# pm-001.net
KiCad netlist of a schematic drawn in EAGLE
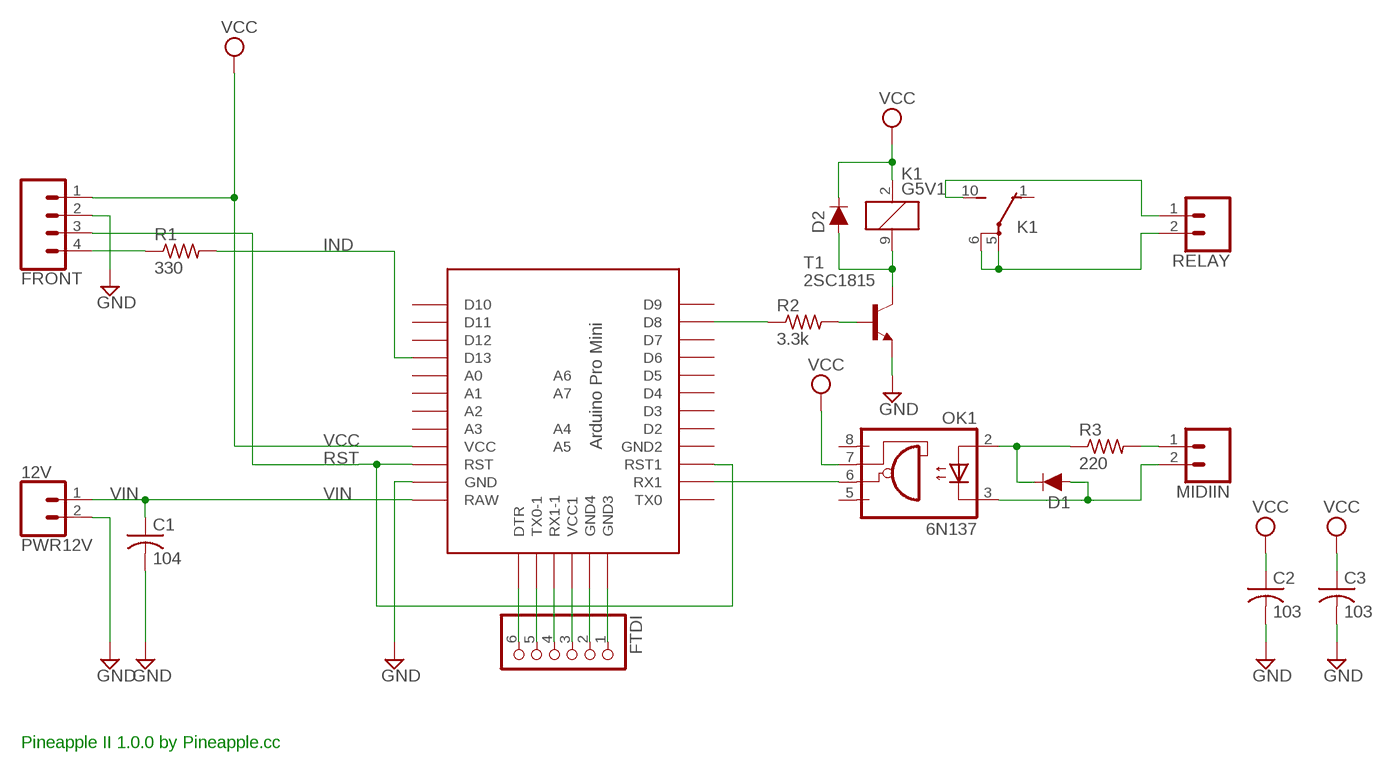
[diagram p0: schematic, sheet 1]

(export (version "E")
  (design (tool "Eeschema 10.0.6"))
  (components
    (comp (ref "C1")
      (value "104")
      (footprint "eagle-import:C025-025X050")
      (libsource (lib "eagle-import") (part "C-US025-025X050"))
    )
    (comp (ref "C2")
      (value "103")
      (footprint "eagle-import:C025-025X050")
      (libsource (lib "eagle-import") (part "C-US025-025X050"))
    )
    (comp (ref "C3")
      (value "103")
      (footprint "eagle-import:C025-025X050")
      (libsource (lib "eagle-import") (part "C-US025-025X050"))
    )
    (comp (ref "D1")
      (value "DIODE-1N4148")
      (footprint "eagle-import:DIODE-1N4148")
      (libsource (lib "eagle-import") (part "DIODE-1N4148"))
    )
    (comp (ref "D2")
      (value "DIODE-1N4148")
      (footprint "eagle-import:DIODE-1N4148")
      (libsource (lib "eagle-import") (part "DIODE-1N4148"))
    )
    (comp (ref "FRONT")
      (value "CONN_04JST-PTH")
      (footprint "eagle-import:JST-4-PTH")
      (libsource (lib "eagle-import") (part "CONN_04JST-PTH"))
    )
    (comp (ref "FTDI")
      (value "PINHD-1X6")
      (footprint "eagle-import:1X06")
      (libsource (lib "eagle-import") (part "PINHD-1X6"))
    )
    (comp (ref "K1")
      (value "G5V1")
      (footprint "eagle-import:G5V1")
      (fields (field (name "MPN") "G5V-1-DC24"))
      (libsource (lib "eagle-import") (part "G5V1"))
    )
    (comp (ref "MIDIIN")
      (value "CONN_02JST-PTH-2")
      (footprint "eagle-import:JST-2-PTH")
      (libsource (lib "eagle-import") (part "CONN_02JST-PTH-2"))
    )
    (comp (ref "OK1")
      (value "6N137")
      (footprint "eagle-import:DIL08")
      (libsource (lib "eagle-import") (part "6N137"))
    )
    (comp (ref "PWR12V")
      (value "12V")
      (footprint "eagle-import:JST-2-PTH")
      (libsource (lib "eagle-import") (part "CONN_02JST-PTH-2"))
    )
    (comp (ref "R1")
      (value "330")
      (footprint "eagle-import:0204_5")
      (libsource (lib "eagle-import") (part "R-US_0204/5"))
    )
    (comp (ref "R2")
      (value "3.3k")
      (footprint "eagle-import:0204_5")
      (libsource (lib "eagle-import") (part "R-US_0204/5"))
    )
    (comp (ref "R3")
      (value "220")
      (footprint "eagle-import:0204_5")
      (libsource (lib "eagle-import") (part "R-US_0204/5"))
    )
    (comp (ref "RELAY")
      (value "CONN_02JST-PTH-2")
      (footprint "eagle-import:JST-2-PTH")
      (libsource (lib "eagle-import") (part "CONN_02JST-PTH-2"))
    )
    (comp (ref "T1")
      (value "2SC1815")
      (footprint "eagle-import:TO92-ECB")
      (libsource (lib "eagle-import") (part "2SC1815"))
    )
    (comp (ref "U$1")
      (value "PRO-MINI-2")
      (footprint "eagle-import:PRO-MINI-2")
      (libsource (lib "eagle-import") (part "PRO-MINI-2"))
    )
  )
  (nets
    (net (code "1") (name "/IND") (class "Default")
      (node (ref "R1") (pin "2") (pinfunction "2_2") (pintype "passive"))
      (node (ref "U$1") (pin "D13") (pinfunction "D13_D13") (pintype "bidirectional"))
    )
    (net (code "2") (name "/RST") (class "Default")
      (node (ref "FRONT") (pin "3") (pinfunction "3_3") (pintype "passive"))
      (node (ref "U$1") (pin "RST") (pinfunction "RST_RST") (pintype "bidirectional"))
      (node (ref "U$1") (pin "RST1") (pinfunction "RST1_RST1") (pintype "bidirectional"))
    )
    (net (code "3") (name "/VIN") (class "Default")
      (node (ref "C1") (pin "1") (pinfunction "1_1") (pintype "passive"))
      (node (ref "PWR12V") (pin "1") (pinfunction "1_1") (pintype "passive"))
      (node (ref "U$1") (pin "RAW") (pinfunction "RAW_RAW") (pintype "bidirectional"))
    )
    (net (code "4") (name "GND") (class "Default")
      (node (ref "C1") (pin "2") (pinfunction "2_2") (pintype "passive"))
      (node (ref "C2") (pin "2") (pinfunction "2_2") (pintype "passive"))
      (node (ref "C3") (pin "2") (pinfunction "2_2") (pintype "passive"))
      (node (ref "FRONT") (pin "2") (pinfunction "2_2") (pintype "passive"))
      (node (ref "PWR12V") (pin "2") (pinfunction "2_2") (pintype "passive"))
      (node (ref "T1") (pin "E") (pinfunction "E_E") (pintype "passive"))
      (node (ref "U$1") (pin "GND") (pinfunction "GND_GND") (pintype "bidirectional"))
    )
    (net (code "5") (name "Net-(FRONT-Pad4)") (class "Default")
      (node (ref "FRONT") (pin "4") (pinfunction "4_4") (pintype "passive"))
      (node (ref "R1") (pin "1") (pinfunction "1_1") (pintype "passive"))
    )
    (net (code "6") (name "Net-(FTDI-Pad3)") (class "Default")
      (node (ref "FTDI") (pin "3") (pinfunction "3_3") (pintype "passive"))
      (node (ref "U$1") (pin "VCC1") (pinfunction "VCC1_VCC1") (pintype "bidirectional"))
    )
    (net (code "7") (name "Net-(FTDI-Pad4)") (class "Default")
      (node (ref "FTDI") (pin "4") (pinfunction "4_4") (pintype "passive"))
      (node (ref "U$1") (pin "RX1-1") (pinfunction "RX1-1_RX1-1") (pintype "bidirectional"))
    )
    (net (code "8") (name "Net-(FTDI-Pad5)") (class "Default")
      (node (ref "FTDI") (pin "5") (pinfunction "5_5") (pintype "passive"))
      (node (ref "U$1") (pin "TX0-1") (pinfunction "TX0-1_TX0-1") (pintype "bidirectional"))
    )
    (net (code "9") (name "Net-(FTDI-Pad6)") (class "Default")
      (node (ref "FTDI") (pin "6") (pinfunction "6_6") (pintype "passive"))
      (node (ref "U$1") (pin "DTR") (pinfunction "DTR_DTR") (pintype "bidirectional"))
    )
    (net (code "10") (name "Net-(K1A-2)") (class "Default")
      (node (ref "D2") (pin "A") (pinfunction "A_A") (pintype "passive"))
      (node (ref "K1") (pin "9") (pinfunction "2_9") (pintype "passive"))
      (node (ref "T1") (pin "C") (pinfunction "C_C") (pintype "passive"))
    )
    (net (code "11") (name "Net-(K1B-P-Pad5)") (class "Default")
      (node (ref "K1") (pin "5") (pinfunction "P_5") (pintype "passive"))
      (node (ref "K1") (pin "6") (pinfunction "P_6") (pintype "passive"))
      (node (ref "RELAY") (pin "2") (pinfunction "2_2") (pintype "passive"))
    )
    (net (code "12") (name "Net-(K1B-S)") (class "Default")
      (node (ref "K1") (pin "10") (pinfunction "S_10") (pintype "passive"))
      (node (ref "RELAY") (pin "1") (pinfunction "1_1") (pintype "passive"))
    )
    (net (code "13") (name "Net-(MIDIIN-Pad1)") (class "Default")
      (node (ref "MIDIIN") (pin "1") (pinfunction "1_1") (pintype "passive"))
      (node (ref "R3") (pin "2") (pinfunction "2_2") (pintype "passive"))
    )
    (net (code "14") (name "Net-(OK1-A)") (class "Default")
      (node (ref "D1") (pin "C") (pinfunction "C_C") (pintype "passive"))
      (node (ref "OK1") (pin "2") (pinfunction "A_2") (pintype "passive"))
      (node (ref "R3") (pin "1") (pinfunction "1_1") (pintype "passive"))
    )
    (net (code "15") (name "Net-(OK1-C)") (class "Default")
      (node (ref "D1") (pin "A") (pinfunction "A_A") (pintype "passive"))
      (node (ref "MIDIIN") (pin "2") (pinfunction "2_2") (pintype "passive"))
      (node (ref "OK1") (pin "3") (pinfunction "C_3") (pintype "passive"))
    )
    (net (code "16") (name "Net-(OK1-VO)") (class "Default")
      (node (ref "OK1") (pin "6") (pinfunction "VO_6") (pintype "passive"))
      (node (ref "U$1") (pin "RX1") (pinfunction "RX1_RX1") (pintype "bidirectional"))
    )
    (net (code "17") (name "Net-(R2-Pad1)") (class "Default")
      (node (ref "R2") (pin "1") (pinfunction "1_1") (pintype "passive"))
      (node (ref "U$1") (pin "D8") (pinfunction "D8_D8") (pintype "bidirectional"))
    )
    (net (code "18") (name "Net-(R2-Pad2)") (class "Default")
      (node (ref "R2") (pin "2") (pinfunction "2_2") (pintype "passive"))
      (node (ref "T1") (pin "B") (pinfunction "B_B") (pintype "passive"))
    )
    (net (code "19") (name "Net-(U$1-GND3)") (class "Default")
      (node (ref "FTDI") (pin "1") (pinfunction "1_1") (pintype "passive"))
      (node (ref "U$1") (pin "GND2") (pinfunction "GND3_GND2") (pintype "bidirectional"))
    )
    (net (code "20") (name "Net-(U$1-GND4)") (class "Default")
      (node (ref "FTDI") (pin "2") (pinfunction "2_2") (pintype "passive"))
      (node (ref "U$1") (pin "GND3") (pinfunction "GND4_GND3") (pintype "bidirectional"))
    )
    (net (code "21") (name "VCC") (class "Default")
      (node (ref "C2") (pin "1") (pinfunction "1_1") (pintype "passive"))
      (node (ref "C3") (pin "1") (pinfunction "1_1") (pintype "passive"))
      (node (ref "D2") (pin "C") (pinfunction "C_C") (pintype "passive"))
      (node (ref "FRONT") (pin "1") (pinfunction "1_1") (pintype "passive"))
      (node (ref "K1") (pin "2") (pinfunction "1_2") (pintype "passive"))
      (node (ref "OK1") (pin "7") (pinfunction "VE_7") (pintype "passive"))
      (node (ref "U$1") (pin "VCC") (pinfunction "VCC_VCC") (pintype "bidirectional"))
    )
    (net (code "22") (name "unconnected-(K1B-O-Pad1)") (class "Default")
      (node (ref "K1") (pin "1") (pinfunction "O_1") (pintype "passive"))
    )
    (net (code "23") (name "unconnected-(OK1-GND-Pad5)") (class "Default")
      (node (ref "OK1") (pin "5") (pinfunction "GND_5") (pintype "passive"))
    )
    (net (code "24") (name "unconnected-(OK1-VCC-Pad8)") (class "Default")
      (node (ref "OK1") (pin "8") (pinfunction "VCC_8") (pintype "passive"))
    )
    (net (code "25") (name "unconnected-(U$1-GND2-PadGND1)") (class "Default")
      (node (ref "U$1") (pin "GND1") (pinfunction "GND2_GND1") (pintype "bidirectional"))
    )
    (net (code "26") (name "unconnected-(U$1-PadA0)") (class "Default")
      (node (ref "U$1") (pin "A0") (pinfunction "A0_A0") (pintype "bidirectional"))
    )
    (net (code "27") (name "unconnected-(U$1-PadA1)") (class "Default")
      (node (ref "U$1") (pin "A1") (pinfunction "A1_A1") (pintype "bidirectional"))
    )
    (net (code "28") (name "unconnected-(U$1-PadA2)") (class "Default")
      (node (ref "U$1") (pin "A2") (pinfunction "A2_A2") (pintype "bidirectional"))
    )
    (net (code "29") (name "unconnected-(U$1-PadA3)") (class "Default")
      (node (ref "U$1") (pin "A3") (pinfunction "A3_A3") (pintype "bidirectional"))
    )
    (net (code "30") (name "unconnected-(U$1-PadA4)") (class "Default")
      (node (ref "U$1") (pin "A4") (pinfunction "A4_A4") (pintype "bidirectional"))
    )
    (net (code "31") (name "unconnected-(U$1-PadA5)") (class "Default")
      (node (ref "U$1") (pin "A5") (pinfunction "A5_A5") (pintype "bidirectional"))
    )
    (net (code "32") (name "unconnected-(U$1-PadA6)") (class "Default")
      (node (ref "U$1") (pin "A6") (pinfunction "A6_A6") (pintype "bidirectional"))
    )
    (net (code "33") (name "unconnected-(U$1-PadA7)") (class "Default")
      (node (ref "U$1") (pin "A7") (pinfunction "A7_A7") (pintype "bidirectional"))
    )
    (net (code "34") (name "unconnected-(U$1-PadD2)") (class "Default")
      (node (ref "U$1") (pin "D2") (pinfunction "D2_D2") (pintype "bidirectional"))
    )
    (net (code "35") (name "unconnected-(U$1-PadD3)") (class "Default")
      (node (ref "U$1") (pin "D3") (pinfunction "D3_D3") (pintype "bidirectional"))
    )
    (net (code "36") (name "unconnected-(U$1-PadD4)") (class "Default")
      (node (ref "U$1") (pin "D4") (pinfunction "D4_D4") (pintype "bidirectional"))
    )
    (net (code "37") (name "unconnected-(U$1-PadD5)") (class "Default")
      (node (ref "U$1") (pin "D5") (pinfunction "D5_D5") (pintype "bidirectional"))
    )
    (net (code "38") (name "unconnected-(U$1-PadD6)") (class "Default")
      (node (ref "U$1") (pin "D6") (pinfunction "D6_D6") (pintype "bidirectional"))
    )
    (net (code "39") (name "unconnected-(U$1-PadD7)") (class "Default")
      (node (ref "U$1") (pin "D7") (pinfunction "D7_D7") (pintype "bidirectional"))
    )
    (net (code "40") (name "unconnected-(U$1-PadD9)") (class "Default")
      (node (ref "U$1") (pin "D9") (pinfunction "D9_D9") (pintype "bidirectional"))
    )
    (net (code "41") (name "unconnected-(U$1-PadD10)") (class "Default")
      (node (ref "U$1") (pin "D10") (pinfunction "D10_D10") (pintype "bidirectional"))
    )
    (net (code "42") (name "unconnected-(U$1-PadD11)") (class "Default")
      (node (ref "U$1") (pin "D11") (pinfunction "D11_D11") (pintype "bidirectional"))
    )
    (net (code "43") (name "unconnected-(U$1-PadD12)") (class "Default")
      (node (ref "U$1") (pin "D12") (pinfunction "D12_D12") (pintype "bidirectional"))
    )
    (net (code "44") (name "unconnected-(U$1-PadTX0)") (class "Default")
      (node (ref "U$1") (pin "TX0") (pinfunction "TX0_TX0") (pintype "bidirectional"))
    )
  )
)
